# ESC.net
KiCad netlist of a schematic drawn in EAGLE
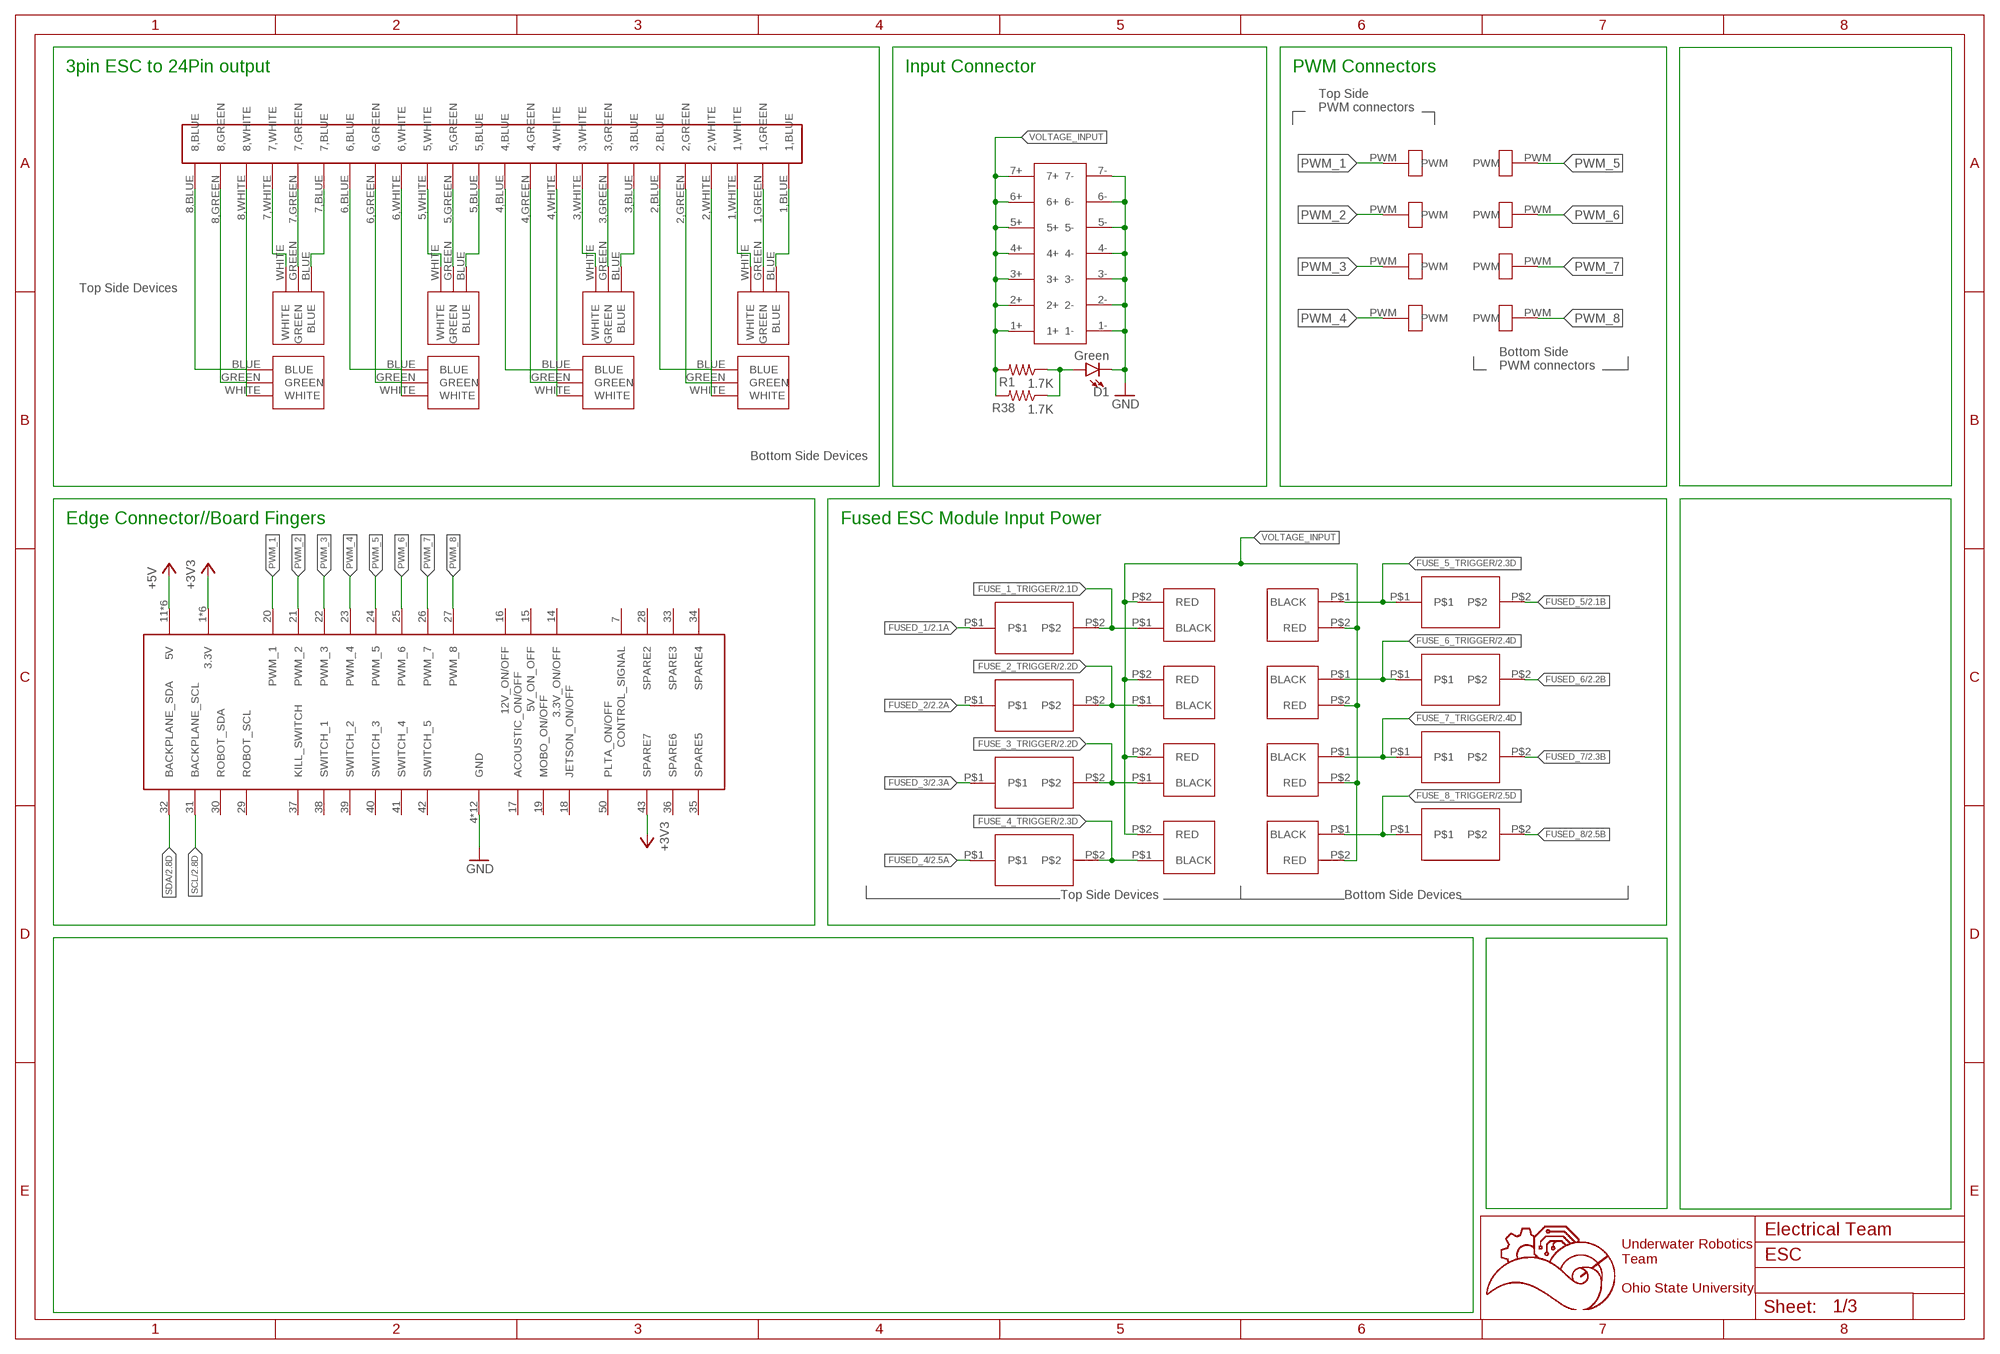
[diagram p0: schematic, sheet 1]
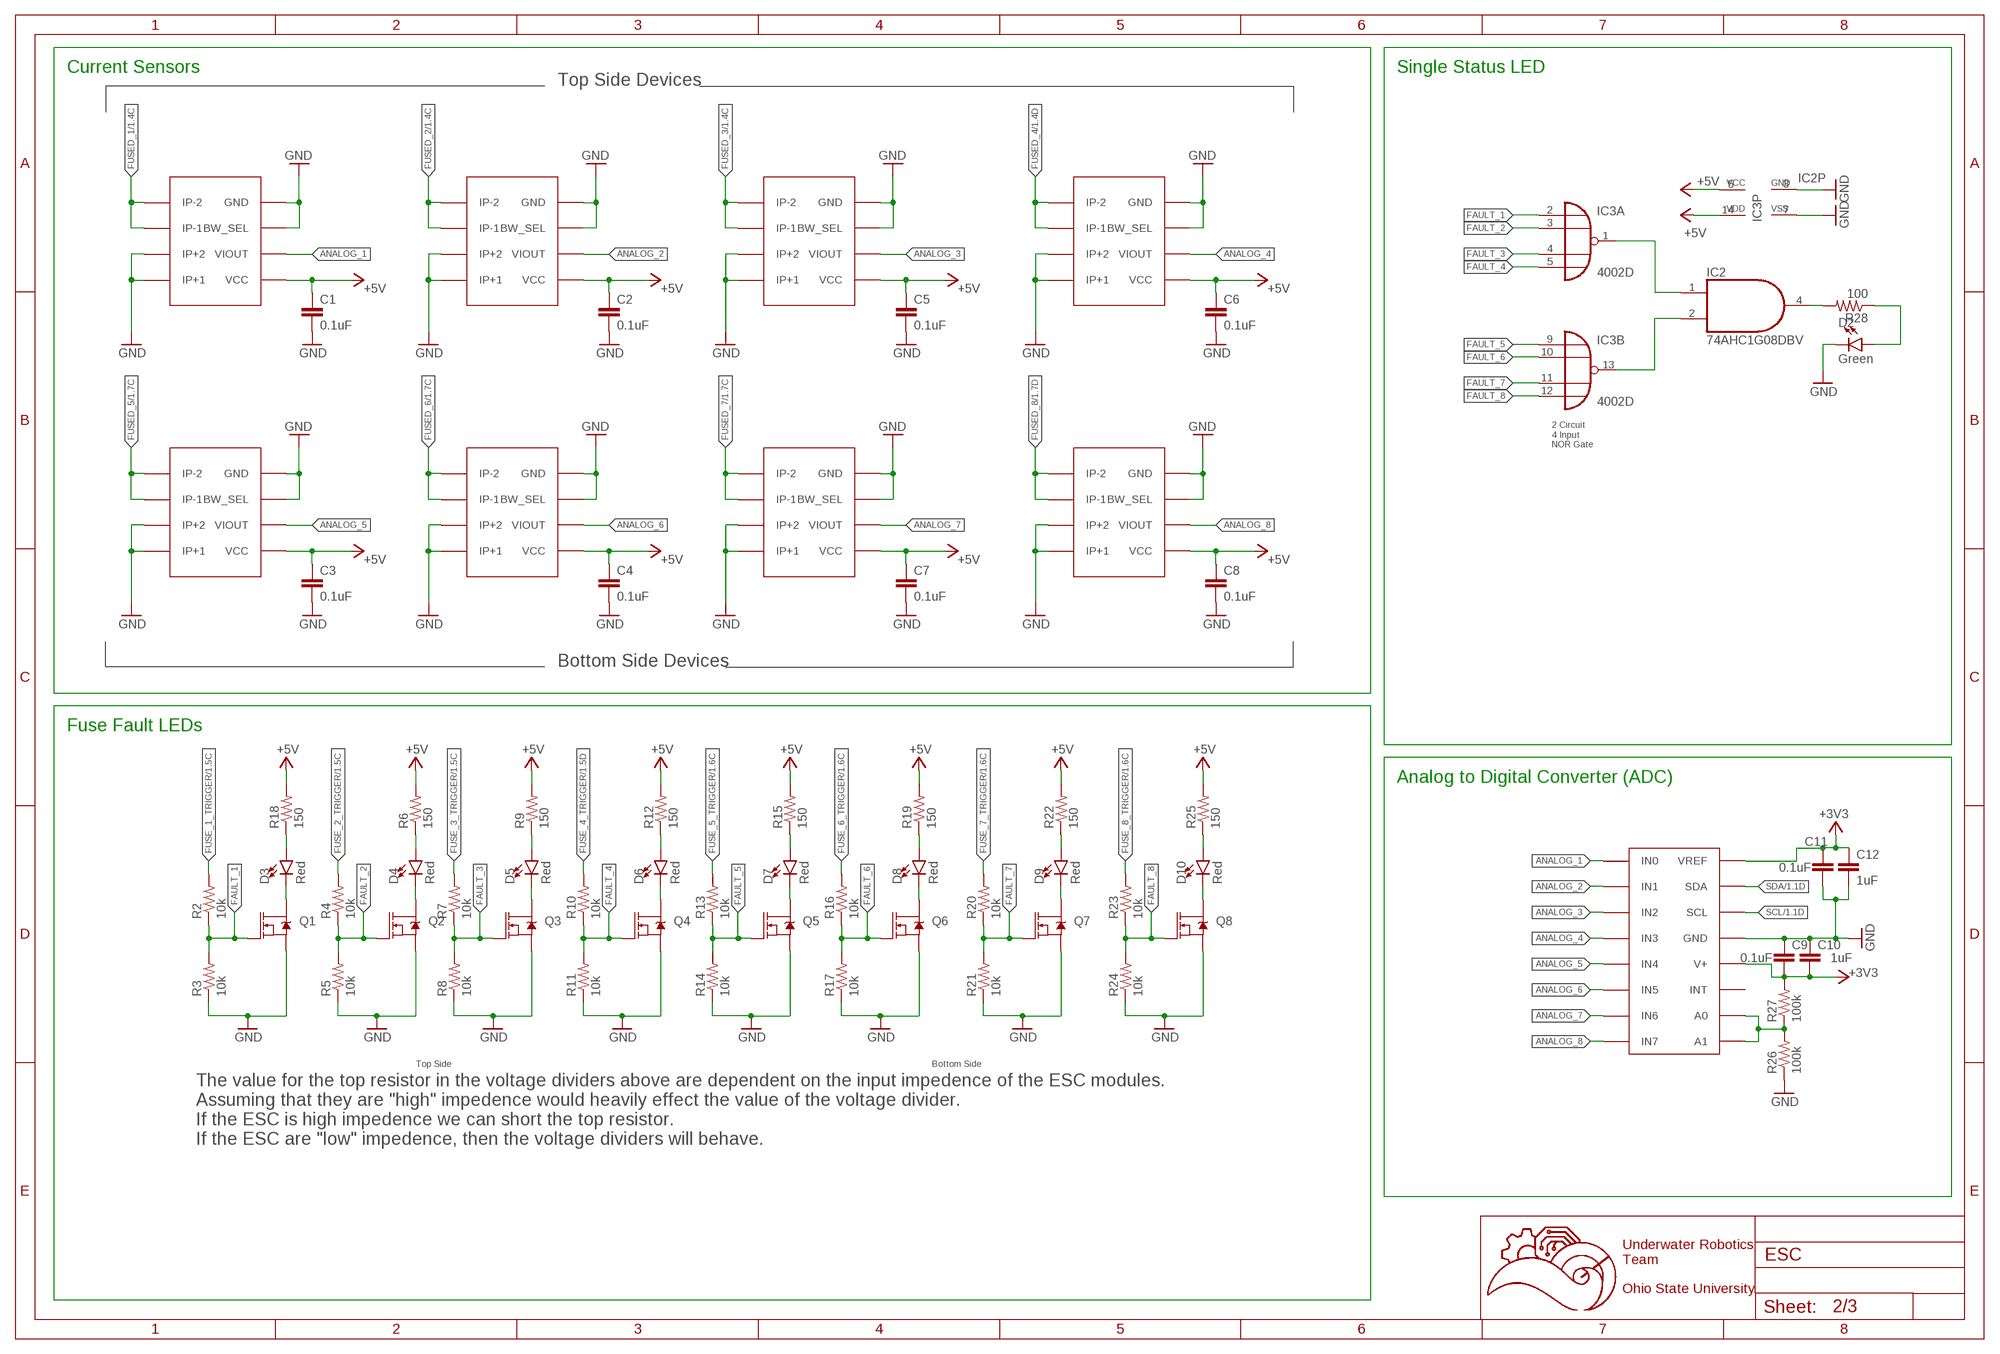
[diagram p1: schematic, sheet 2]
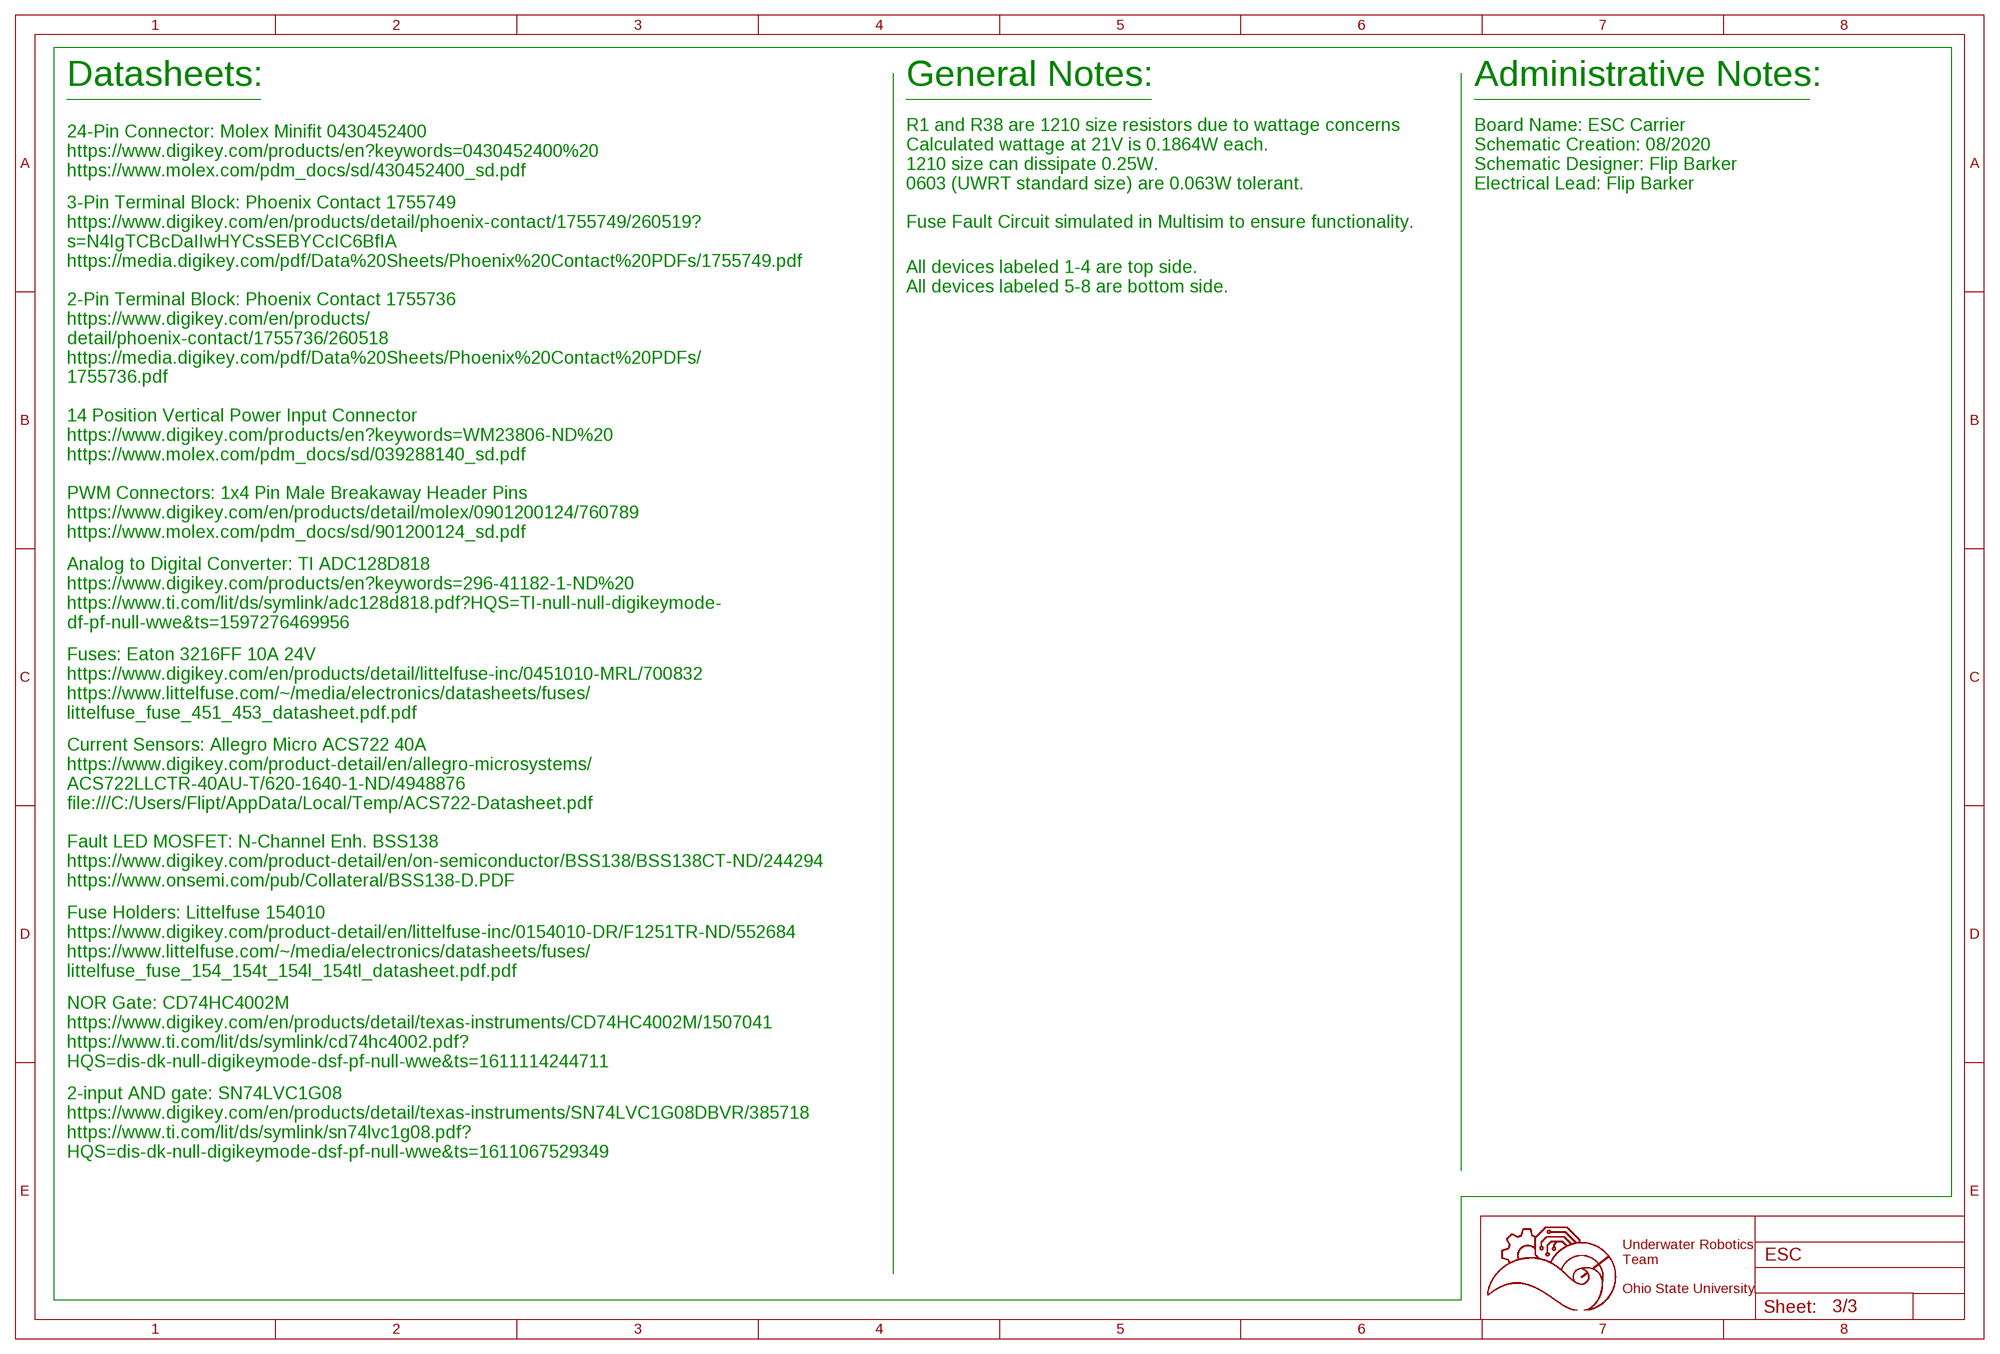
[diagram p2: schematic, sheet 3]

(export (version "E")
  (design (tool "Eeschema 10.0.6"))
  (components
    (comp (ref "C1")
      (value "0.1uF")
      (footprint "eagle-import:C0603")
      (libsource (lib "eagle-import") (part "C-EUC0603"))
    )
    (comp (ref "C2")
      (value "0.1uF")
      (footprint "eagle-import:C0603")
      (libsource (lib "eagle-import") (part "C-EUC0603"))
    )
    (comp (ref "C3")
      (value "0.1uF")
      (footprint "eagle-import:C0603")
      (libsource (lib "eagle-import") (part "C-EUC0603"))
    )
    (comp (ref "C4")
      (value "0.1uF")
      (footprint "eagle-import:C0603")
      (libsource (lib "eagle-import") (part "C-EUC0603"))
    )
    (comp (ref "C5")
      (value "0.1uF")
      (footprint "eagle-import:C0603")
      (libsource (lib "eagle-import") (part "C-EUC0603"))
    )
    (comp (ref "C6")
      (value "0.1uF")
      (footprint "eagle-import:C0603")
      (libsource (lib "eagle-import") (part "C-EUC0603"))
    )
    (comp (ref "C7")
      (value "0.1uF")
      (footprint "eagle-import:C0603")
      (libsource (lib "eagle-import") (part "C-EUC0603"))
    )
    (comp (ref "C8")
      (value "0.1uF")
      (footprint "eagle-import:C0603")
      (libsource (lib "eagle-import") (part "C-EUC0603"))
    )
    (comp (ref "C9")
      (value "0.1uF")
      (footprint "eagle-import:C0603")
      (libsource (lib "eagle-import") (part "C-EUC0603"))
    )
    (comp (ref "C10")
      (value "1uF")
      (footprint "eagle-import:C0603")
      (libsource (lib "eagle-import") (part "C-EUC0603"))
    )
    (comp (ref "C11")
      (value "0.1uF")
      (footprint "eagle-import:C0603")
      (libsource (lib "eagle-import") (part "C-EUC0603"))
    )
    (comp (ref "C12")
      (value "1uF")
      (footprint "eagle-import:C0603")
      (libsource (lib "eagle-import") (part "C-EUC0603"))
    )
    (comp (ref "CS_1")
      (value "ACS722")
      (footprint "eagle-import:SOIC-8")
      (libsource (lib "eagle-import") (part "ACS722"))
    )
    (comp (ref "CS_2")
      (value "ACS722")
      (footprint "eagle-import:SOIC-8")
      (libsource (lib "eagle-import") (part "ACS722"))
    )
    (comp (ref "CS_3")
      (value "ACS722")
      (footprint "eagle-import:SOIC-8")
      (libsource (lib "eagle-import") (part "ACS722"))
    )
    (comp (ref "CS_4")
      (value "ACS722")
      (footprint "eagle-import:SOIC-8")
      (libsource (lib "eagle-import") (part "ACS722"))
    )
    (comp (ref "CS_5")
      (value "ACS722")
      (footprint "eagle-import:SOIC-8")
      (libsource (lib "eagle-import") (part "ACS722"))
    )
    (comp (ref "CS_6")
      (value "ACS722")
      (footprint "eagle-import:SOIC-8")
      (libsource (lib "eagle-import") (part "ACS722"))
    )
    (comp (ref "CS_7")
      (value "ACS722")
      (footprint "eagle-import:SOIC-8")
      (libsource (lib "eagle-import") (part "ACS722"))
    )
    (comp (ref "CS_8")
      (value "ACS722")
      (footprint "eagle-import:SOIC-8")
      (libsource (lib "eagle-import") (part "ACS722"))
    )
    (comp (ref "D2")
      (value "Green")
      (footprint "eagle-import:LED-0603")
      (libsource (lib "eagle-import") (part "LED0603"))
    )
    (comp (ref "D3")
      (value "Red")
      (footprint "eagle-import:LED-0603")
      (libsource (lib "eagle-import") (part "LED0603"))
    )
    (comp (ref "D4")
      (value "Red")
      (footprint "eagle-import:LED-0603")
      (libsource (lib "eagle-import") (part "LED0603"))
    )
    (comp (ref "D5")
      (value "Red")
      (footprint "eagle-import:LED-0603")
      (libsource (lib "eagle-import") (part "LED0603"))
    )
    (comp (ref "D6")
      (value "Red")
      (footprint "eagle-import:LED-0603")
      (libsource (lib "eagle-import") (part "LED0603"))
    )
    (comp (ref "D7")
      (value "Red")
      (footprint "eagle-import:LED-0603")
      (libsource (lib "eagle-import") (part "LED0603"))
    )
    (comp (ref "D8")
      (value "Red")
      (footprint "eagle-import:LED-0603")
      (libsource (lib "eagle-import") (part "LED0603"))
    )
    (comp (ref "D9")
      (value "Red")
      (footprint "eagle-import:LED-0603")
      (libsource (lib "eagle-import") (part "LED0603"))
    )
    (comp (ref "D10")
      (value "Red")
      (footprint "eagle-import:LED-0603")
      (libsource (lib "eagle-import") (part "LED0603"))
    )
    (comp (ref "IC2")
      (value "74AHC1G08DBV")
      (footprint "eagle-import:SOT23-5")
      (libsource (lib "eagle-import") (part "741G08DBVAHC"))
    )
    (comp (ref "IC3")
      (value "4002D")
      (footprint "eagle-import:SO14")
      (libsource (lib "eagle-import") (part "4002D"))
    )
    (comp (ref "Q1")
      (value "5.8A/30V/35mΩ")
      (footprint "eagle-import:SOT23-3")
      (libsource (lib "eagle-import") (part "MOSFET-NCH-AO3404A"))
    )
    (comp (ref "Q2")
      (value "5.8A/30V/35mΩ")
      (footprint "eagle-import:SOT23-3")
      (libsource (lib "eagle-import") (part "MOSFET-NCH-AO3404A"))
    )
    (comp (ref "Q3")
      (value "5.8A/30V/35mΩ")
      (footprint "eagle-import:SOT23-3")
      (libsource (lib "eagle-import") (part "MOSFET-NCH-AO3404A"))
    )
    (comp (ref "Q4")
      (value "5.8A/30V/35mΩ")
      (footprint "eagle-import:SOT23-3")
      (libsource (lib "eagle-import") (part "MOSFET-NCH-AO3404A"))
    )
    (comp (ref "Q5")
      (value "5.8A/30V/35mΩ")
      (footprint "eagle-import:SOT23-3")
      (libsource (lib "eagle-import") (part "MOSFET-NCH-AO3404A"))
    )
    (comp (ref "Q6")
      (value "5.8A/30V/35mΩ")
      (footprint "eagle-import:SOT23-3")
      (libsource (lib "eagle-import") (part "MOSFET-NCH-AO3404A"))
    )
    (comp (ref "Q7")
      (value "5.8A/30V/35mΩ")
      (footprint "eagle-import:SOT23-3")
      (libsource (lib "eagle-import") (part "MOSFET-NCH-AO3404A"))
    )
    (comp (ref "Q8")
      (value "5.8A/30V/35mΩ")
      (footprint "eagle-import:SOT23-3")
      (libsource (lib "eagle-import") (part "MOSFET-NCH-AO3404A"))
    )
    (comp (ref "R2")
      (value "10k")
      (footprint "eagle-import:R0603")
      (libsource (lib "eagle-import") (part "R-US_R0603"))
    )
    (comp (ref "R3")
      (value "10k")
      (footprint "eagle-import:R0603")
      (libsource (lib "eagle-import") (part "R-US_R0603"))
    )
    (comp (ref "R4")
      (value "10k")
      (footprint "eagle-import:R0603")
      (libsource (lib "eagle-import") (part "R-US_R0603"))
    )
    (comp (ref "R5")
      (value "10k")
      (footprint "eagle-import:R0603")
      (libsource (lib "eagle-import") (part "R-US_R0603"))
    )
    (comp (ref "R6")
      (value "150")
      (footprint "eagle-import:R0603")
      (libsource (lib "eagle-import") (part "R-US_R0603"))
    )
    (comp (ref "R7")
      (value "10k")
      (footprint "eagle-import:R0603")
      (libsource (lib "eagle-import") (part "R-US_R0603"))
    )
    (comp (ref "R8")
      (value "10k")
      (footprint "eagle-import:R0603")
      (libsource (lib "eagle-import") (part "R-US_R0603"))
    )
    (comp (ref "R9")
      (value "150")
      (footprint "eagle-import:R0603")
      (libsource (lib "eagle-import") (part "R-US_R0603"))
    )
    (comp (ref "R10")
      (value "10k")
      (footprint "eagle-import:R0603")
      (libsource (lib "eagle-import") (part "R-US_R0603"))
    )
    (comp (ref "R11")
      (value "10k")
      (footprint "eagle-import:R0603")
      (libsource (lib "eagle-import") (part "R-US_R0603"))
    )
    (comp (ref "R12")
      (value "150")
      (footprint "eagle-import:R0603")
      (libsource (lib "eagle-import") (part "R-US_R0603"))
    )
    (comp (ref "R13")
      (value "10k")
      (footprint "eagle-import:R0603")
      (libsource (lib "eagle-import") (part "R-US_R0603"))
    )
    (comp (ref "R14")
      (value "10k")
      (footprint "eagle-import:R0603")
      (libsource (lib "eagle-import") (part "R-US_R0603"))
    )
    (comp (ref "R15")
      (value "150")
      (footprint "eagle-import:R0603")
      (libsource (lib "eagle-import") (part "R-US_R0603"))
    )
    (comp (ref "R16")
      (value "10k")
      (footprint "eagle-import:R0603")
      (libsource (lib "eagle-import") (part "R-US_R0603"))
    )
    (comp (ref "R17")
      (value "10k")
      (footprint "eagle-import:R0603")
      (libsource (lib "eagle-import") (part "R-US_R0603"))
    )
    (comp (ref "R18")
      (value "150")
      (footprint "eagle-import:R0603")
      (libsource (lib "eagle-import") (part "R-US_R0603"))
    )
    (comp (ref "R19")
      (value "150")
      (footprint "eagle-import:R0603")
      (libsource (lib "eagle-import") (part "R-US_R0603"))
    )
    (comp (ref "R20")
      (value "10k")
      (footprint "eagle-import:R0603")
      (libsource (lib "eagle-import") (part "R-US_R0603"))
    )
    (comp (ref "R21")
      (value "10k")
      (footprint "eagle-import:R0603")
      (libsource (lib "eagle-import") (part "R-US_R0603"))
    )
    (comp (ref "R22")
      (value "150")
      (footprint "eagle-import:R0603")
      (libsource (lib "eagle-import") (part "R-US_R0603"))
    )
    (comp (ref "R23")
      (value "10k")
      (footprint "eagle-import:R0603")
      (libsource (lib "eagle-import") (part "R-US_R0603"))
    )
    (comp (ref "R24")
      (value "10k")
      (footprint "eagle-import:R0603")
      (libsource (lib "eagle-import") (part "R-US_R0603"))
    )
    (comp (ref "R25")
      (value "150")
      (footprint "eagle-import:R0603")
      (libsource (lib "eagle-import") (part "R-US_R0603"))
    )
    (comp (ref "R26")
      (value "100k")
      (footprint "eagle-import:R0603")
      (libsource (lib "eagle-import") (part "R-US_R0603"))
    )
    (comp (ref "R27")
      (value "100k")
      (footprint "eagle-import:R0603")
      (libsource (lib "eagle-import") (part "R-US_R0603"))
    )
    (comp (ref "R28")
      (value "100")
      (footprint "eagle-import:R0603")
      (libsource (lib "eagle-import") (part "R-US_R0603"))
    )
    (comp (ref "U$11")
      (value "ADC128D818")
      (footprint "eagle-import:TSSOP-16")
      (libsource (lib "eagle-import") (part "ADC128D818"))
    )
    (comp (ref "2-PIN_1")
      (value "1755736")
      (footprint "eagle-import:1755736")
      (libsource (lib "eagle-import") (part "1755736"))
    )
    (comp (ref "2-PIN_2")
      (value "1755736")
      (footprint "eagle-import:1755736")
      (libsource (lib "eagle-import") (part "1755736"))
    )
    (comp (ref "2-PIN_3")
      (value "1755736")
      (footprint "eagle-import:1755736")
      (libsource (lib "eagle-import") (part "1755736"))
    )
    (comp (ref "2-PIN_4")
      (value "1755736")
      (footprint "eagle-import:1755736")
      (libsource (lib "eagle-import") (part "1755736"))
    )
    (comp (ref "2-PIN_5")
      (value "1755736")
      (footprint "eagle-import:1755736")
      (libsource (lib "eagle-import") (part "1755736"))
    )
    (comp (ref "2-PIN_6")
      (value "1755736")
      (footprint "eagle-import:1755736")
      (libsource (lib "eagle-import") (part "1755736"))
    )
    (comp (ref "2-PIN_7")
      (value "1755736")
      (footprint "eagle-import:1755736")
      (libsource (lib "eagle-import") (part "1755736"))
    )
    (comp (ref "2-PIN_8")
      (value "1755736")
      (footprint "eagle-import:1755736")
      (libsource (lib "eagle-import") (part "1755736"))
    )
    (comp (ref "3-PIN_1")
      (value "1755749")
      (footprint "eagle-import:1755749")
      (libsource (lib "eagle-import") (part "1755749"))
    )
    (comp (ref "3-PIN_2")
      (value "1755749")
      (footprint "eagle-import:1755749")
      (libsource (lib "eagle-import") (part "1755749"))
    )
    (comp (ref "3-PIN_3")
      (value "1755749")
      (footprint "eagle-import:1755749")
      (libsource (lib "eagle-import") (part "1755749"))
    )
    (comp (ref "3-PIN_4")
      (value "1755749")
      (footprint "eagle-import:1755749")
      (libsource (lib "eagle-import") (part "1755749"))
    )
    (comp (ref "3-PIN_5")
      (value "1755749")
      (footprint "eagle-import:1755749")
      (libsource (lib "eagle-import") (part "1755749"))
    )
    (comp (ref "3-PIN_6")
      (value "1755749")
      (footprint "eagle-import:1755749")
      (libsource (lib "eagle-import") (part "1755749"))
    )
    (comp (ref "3-PIN_7")
      (value "1755749")
      (footprint "eagle-import:1755749")
      (libsource (lib "eagle-import") (part "1755749"))
    )
    (comp (ref "3-PIN_8")
      (value "1755749")
      (footprint "eagle-import:1755749")
      (libsource (lib "eagle-import") (part "1755749"))
    )
    (comp (ref "24-PIN_CONNECTOR")
      (value "24PINCONVERTER")
      (footprint "eagle-import:24PINCONVERTER")
      (libsource (lib "eagle-import") (part "24PINCONVERTER"))
    )
    (comp (ref "D1")
      (value "Green")
      (footprint "eagle-import:LED-0603")
      (libsource (lib "eagle-import") (part "LED0603"))
    )
    (comp (ref "EDGE_CONNECTOR")
      (value "5530843-EDGE")
      (footprint "eagle-import:5530843-6-BOARDFINGERS")
      (libsource (lib "eagle-import") (part "5530843-EDGE"))
    )
    (comp (ref "F1")
      (value "1206FUSEHOLDER")
      (footprint "eagle-import:1206FUSEHOLDER")
      (libsource (lib "eagle-import") (part "1206FUSEHOLDER"))
    )
    (comp (ref "F2")
      (value "1206FUSEHOLDER")
      (footprint "eagle-import:1206FUSEHOLDER")
      (libsource (lib "eagle-import") (part "1206FUSEHOLDER"))
    )
    (comp (ref "F3")
      (value "1206FUSEHOLDER")
      (footprint "eagle-import:1206FUSEHOLDER")
      (libsource (lib "eagle-import") (part "1206FUSEHOLDER"))
    )
    (comp (ref "F4")
      (value "1206FUSEHOLDER")
      (footprint "eagle-import:1206FUSEHOLDER")
      (libsource (lib "eagle-import") (part "1206FUSEHOLDER"))
    )
    (comp (ref "F5")
      (value "1206FUSEHOLDER")
      (footprint "eagle-import:1206FUSEHOLDER")
      (libsource (lib "eagle-import") (part "1206FUSEHOLDER"))
    )
    (comp (ref "F6")
      (value "1206FUSEHOLDER")
      (footprint "eagle-import:1206FUSEHOLDER")
      (libsource (lib "eagle-import") (part "1206FUSEHOLDER"))
    )
    (comp (ref "F7")
      (value "1206FUSEHOLDER")
      (footprint "eagle-import:1206FUSEHOLDER")
      (libsource (lib "eagle-import") (part "1206FUSEHOLDER"))
    )
    (comp (ref "F8")
      (value "1206FUSEHOLDER")
      (footprint "eagle-import:1206FUSEHOLDER")
      (libsource (lib "eagle-import") (part "1206FUSEHOLDER"))
    )
    (comp (ref "POWER_INPUT")
      (value "14PIN_VERT")
      (footprint "eagle-import:14PIN_VERT")
      (libsource (lib "eagle-import") (part "14PIN_VERT"))
    )
    (comp (ref "R1")
      (value "1.7K")
      (footprint "eagle-import:R1210")
      (libsource (lib "eagle-import") (part "R-US_R1210"))
    )
    (comp (ref "R38")
      (value "1.7K")
      (footprint "eagle-import:R1210")
      (libsource (lib "eagle-import") (part "R-US_R1210"))
    )
    (comp (ref "U$1")
      (value "MALE1PINHEADER")
      (footprint "eagle-import:MALE1PINHEADER")
      (libsource (lib "eagle-import") (part "MALE1PINHEADER"))
    )
    (comp (ref "U$2")
      (value "MALE1PINHEADER")
      (footprint "eagle-import:MALE1PINHEADER")
      (libsource (lib "eagle-import") (part "MALE1PINHEADER"))
    )
    (comp (ref "U$3")
      (value "MALE1PINHEADER")
      (footprint "eagle-import:MALE1PINHEADER")
      (libsource (lib "eagle-import") (part "MALE1PINHEADER"))
    )
    (comp (ref "U$4")
      (value "MALE1PINHEADER")
      (footprint "eagle-import:MALE1PINHEADER")
      (libsource (lib "eagle-import") (part "MALE1PINHEADER"))
    )
    (comp (ref "U$5")
      (value "MALE1PINHEADER")
      (footprint "eagle-import:MALE1PINHEADER")
      (libsource (lib "eagle-import") (part "MALE1PINHEADER"))
    )
    (comp (ref "U$6")
      (value "MALE1PINHEADER")
      (footprint "eagle-import:MALE1PINHEADER")
      (libsource (lib "eagle-import") (part "MALE1PINHEADER"))
    )
    (comp (ref "U$7")
      (value "MALE1PINHEADER")
      (footprint "eagle-import:MALE1PINHEADER")
      (libsource (lib "eagle-import") (part "MALE1PINHEADER"))
    )
    (comp (ref "U$8")
      (value "MALE1PINHEADER")
      (footprint "eagle-import:MALE1PINHEADER")
      (libsource (lib "eagle-import") (part "MALE1PINHEADER"))
    )
  )
  (nets
    (net (code "1") (name "+3V3") (class "Default")
      (node (ref "C10") (pin "2") (pinfunction "2_2") (pintype "passive"))
      (node (ref "C11") (pin "1") (pinfunction "1_1") (pintype "passive"))
      (node (ref "C12") (pin "1") (pinfunction "1_1") (pintype "passive"))
      (node (ref "C9") (pin "2") (pinfunction "2_2") (pintype "passive"))
      (node (ref "EDGE_CONNECTOR") (pin "1") (pinfunction "3.3V_1") (pintype "bidirectional"))
      (node (ref "EDGE_CONNECTOR") (pin "2") (pinfunction "3.3V_2") (pintype "bidirectional"))
      (node (ref "EDGE_CONNECTOR") (pin "3") (pinfunction "3.3V_3") (pintype "bidirectional"))
      (node (ref "EDGE_CONNECTOR") (pin "43") (pinfunction "SPARE7_43") (pintype "bidirectional"))
      (node (ref "EDGE_CONNECTOR") (pin "54") (pinfunction "3.3V_54") (pintype "bidirectional"))
      (node (ref "EDGE_CONNECTOR") (pin "55") (pinfunction "3.3V_55") (pintype "bidirectional"))
      (node (ref "EDGE_CONNECTOR") (pin "56") (pinfunction "3.3V_56") (pintype "bidirectional"))
      (node (ref "R27") (pin "2") (pinfunction "2_2") (pintype "passive"))
      (node (ref "U$11") (pin "V+") (pinfunction "V+_V+") (pintype "bidirectional"))
      (node (ref "U$11") (pin "VREF") (pinfunction "VREF_VREF") (pintype "bidirectional"))
    )
    (net (code "2") (name "+5V") (class "Default")
      (node (ref "C1") (pin "1") (pinfunction "1_1") (pintype "passive"))
      (node (ref "C2") (pin "1") (pinfunction "1_1") (pintype "passive"))
      (node (ref "C3") (pin "1") (pinfunction "1_1") (pintype "passive"))
      (node (ref "C4") (pin "1") (pinfunction "1_1") (pintype "passive"))
      (node (ref "C5") (pin "1") (pinfunction "1_1") (pintype "passive"))
      (node (ref "C6") (pin "1") (pinfunction "1_1") (pintype "passive"))
      (node (ref "C7") (pin "1") (pinfunction "1_1") (pintype "passive"))
      (node (ref "C8") (pin "1") (pinfunction "1_1") (pintype "passive"))
      (node (ref "CS_1") (pin "VCC") (pinfunction "VCC_VCC") (pintype "bidirectional"))
      (node (ref "CS_2") (pin "VCC") (pinfunction "VCC_VCC") (pintype "bidirectional"))
      (node (ref "CS_3") (pin "VCC") (pinfunction "VCC_VCC") (pintype "bidirectional"))
      (node (ref "CS_4") (pin "VCC") (pinfunction "VCC_VCC") (pintype "bidirectional"))
      (node (ref "CS_5") (pin "VCC") (pinfunction "VCC_VCC") (pintype "bidirectional"))
      (node (ref "CS_6") (pin "VCC") (pinfunction "VCC_VCC") (pintype "bidirectional"))
      (node (ref "CS_7") (pin "VCC") (pinfunction "VCC_VCC") (pintype "bidirectional"))
      (node (ref "CS_8") (pin "VCC") (pinfunction "VCC_VCC") (pintype "bidirectional"))
      (node (ref "EDGE_CONNECTOR") (pin "11") (pinfunction "5V_11") (pintype "bidirectional"))
      (node (ref "EDGE_CONNECTOR") (pin "12") (pinfunction "5V_12") (pintype "bidirectional"))
      (node (ref "EDGE_CONNECTOR") (pin "13") (pinfunction "5V_13") (pintype "bidirectional"))
      (node (ref "EDGE_CONNECTOR") (pin "44") (pinfunction "5V_44") (pintype "bidirectional"))
      (node (ref "EDGE_CONNECTOR") (pin "45") (pinfunction "5V_45") (pintype "bidirectional"))
      (node (ref "EDGE_CONNECTOR") (pin "46") (pinfunction "5V_46") (pintype "bidirectional"))
      (node (ref "IC2") (pin "5") (pinfunction "VCC_5") (pintype "power_in"))
      (node (ref "IC3") (pin "14") (pinfunction "VDD_14") (pintype "power_in"))
      (node (ref "R12") (pin "2") (pinfunction "2_2") (pintype "passive"))
      (node (ref "R15") (pin "2") (pinfunction "2_2") (pintype "passive"))
      (node (ref "R18") (pin "2") (pinfunction "2_2") (pintype "passive"))
      (node (ref "R19") (pin "2") (pinfunction "2_2") (pintype "passive"))
      (node (ref "R22") (pin "2") (pinfunction "2_2") (pintype "passive"))
      (node (ref "R25") (pin "2") (pinfunction "2_2") (pintype "passive"))
      (node (ref "R6") (pin "2") (pinfunction "2_2") (pintype "passive"))
      (node (ref "R9") (pin "2") (pinfunction "2_2") (pintype "passive"))
    )
    (net (code "3") (name "ANALOG_1") (class "Default")
      (node (ref "CS_1") (pin "VIOUT") (pinfunction "VIOUT_VIOUT") (pintype "bidirectional"))
      (node (ref "U$11") (pin "IN0") (pinfunction "IN0_IN0") (pintype "bidirectional"))
    )
    (net (code "4") (name "ANALOG_2") (class "Default")
      (node (ref "CS_2") (pin "VIOUT") (pinfunction "VIOUT_VIOUT") (pintype "bidirectional"))
      (node (ref "U$11") (pin "IN1") (pinfunction "IN1_IN1") (pintype "bidirectional"))
    )
    (net (code "5") (name "ANALOG_3") (class "Default")
      (node (ref "CS_3") (pin "VIOUT") (pinfunction "VIOUT_VIOUT") (pintype "bidirectional"))
      (node (ref "U$11") (pin "IN2") (pinfunction "IN2_IN2") (pintype "bidirectional"))
    )
    (net (code "6") (name "ANALOG_4") (class "Default")
      (node (ref "CS_4") (pin "VIOUT") (pinfunction "VIOUT_VIOUT") (pintype "bidirectional"))
      (node (ref "U$11") (pin "IN3") (pinfunction "IN3_IN3") (pintype "bidirectional"))
    )
    (net (code "7") (name "ANALOG_5") (class "Default")
      (node (ref "CS_5") (pin "VIOUT") (pinfunction "VIOUT_VIOUT") (pintype "bidirectional"))
      (node (ref "U$11") (pin "IN4") (pinfunction "IN4_IN4") (pintype "bidirectional"))
    )
    (net (code "8") (name "ANALOG_6") (class "Default")
      (node (ref "CS_6") (pin "VIOUT") (pinfunction "VIOUT_VIOUT") (pintype "bidirectional"))
      (node (ref "U$11") (pin "IN5") (pinfunction "IN5_IN5") (pintype "bidirectional"))
    )
    (net (code "9") (name "ANALOG_7") (class "Default")
      (node (ref "CS_7") (pin "VIOUT") (pinfunction "VIOUT_VIOUT") (pintype "bidirectional"))
      (node (ref "U$11") (pin "IN6") (pinfunction "IN6_IN6") (pintype "bidirectional"))
    )
    (net (code "10") (name "ANALOG_8") (class "Default")
      (node (ref "CS_8") (pin "VIOUT") (pinfunction "VIOUT_VIOUT") (pintype "bidirectional"))
      (node (ref "U$11") (pin "IN7") (pinfunction "IN7_IN7") (pintype "bidirectional"))
    )
    (net (code "11") (name "FAULT_1") (class "Default")
      (node (ref "IC3") (pin "2") (pinfunction "I0_2") (pintype "input"))
      (node (ref "Q1") (pin "1") (pinfunction "G_1") (pintype "bidirectional"))
      (node (ref "R2") (pin "1") (pinfunction "1_1") (pintype "passive"))
      (node (ref "R3") (pin "2") (pinfunction "2_2") (pintype "passive"))
    )
    (net (code "12") (name "FAULT_2") (class "Default")
      (node (ref "IC3") (pin "3") (pinfunction "I1_3") (pintype "input"))
      (node (ref "Q2") (pin "1") (pinfunction "G_1") (pintype "bidirectional"))
      (node (ref "R4") (pin "1") (pinfunction "1_1") (pintype "passive"))
      (node (ref "R5") (pin "2") (pinfunction "2_2") (pintype "passive"))
    )
    (net (code "13") (name "FAULT_3") (class "Default")
      (node (ref "IC3") (pin "4") (pinfunction "I2_4") (pintype "input"))
      (node (ref "Q3") (pin "1") (pinfunction "G_1") (pintype "bidirectional"))
      (node (ref "R7") (pin "1") (pinfunction "1_1") (pintype "passive"))
      (node (ref "R8") (pin "2") (pinfunction "2_2") (pintype "passive"))
    )
    (net (code "14") (name "FAULT_4") (class "Default")
      (node (ref "IC3") (pin "5") (pinfunction "I3_5") (pintype "input"))
      (node (ref "Q4") (pin "1") (pinfunction "G_1") (pintype "bidirectional"))
      (node (ref "R10") (pin "1") (pinfunction "1_1") (pintype "passive"))
      (node (ref "R11") (pin "2") (pinfunction "2_2") (pintype "passive"))
    )
    (net (code "15") (name "FAULT_5") (class "Default")
      (node (ref "IC3") (pin "9") (pinfunction "I0_9") (pintype "input"))
      (node (ref "Q5") (pin "1") (pinfunction "G_1") (pintype "bidirectional"))
      (node (ref "R13") (pin "1") (pinfunction "1_1") (pintype "passive"))
      (node (ref "R14") (pin "2") (pinfunction "2_2") (pintype "passive"))
    )
    (net (code "16") (name "FAULT_6") (class "Default")
      (node (ref "IC3") (pin "10") (pinfunction "I1_10") (pintype "input"))
      (node (ref "Q6") (pin "1") (pinfunction "G_1") (pintype "bidirectional"))
      (node (ref "R16") (pin "1") (pinfunction "1_1") (pintype "passive"))
      (node (ref "R17") (pin "2") (pinfunction "2_2") (pintype "passive"))
    )
    (net (code "17") (name "FAULT_7") (class "Default")
      (node (ref "IC3") (pin "11") (pinfunction "I2_11") (pintype "input"))
      (node (ref "Q7") (pin "1") (pinfunction "G_1") (pintype "bidirectional"))
      (node (ref "R20") (pin "1") (pinfunction "1_1") (pintype "passive"))
      (node (ref "R21") (pin "2") (pinfunction "2_2") (pintype "passive"))
    )
    (net (code "18") (name "FAULT_8") (class "Default")
      (node (ref "IC3") (pin "12") (pinfunction "I3_12") (pintype "input"))
      (node (ref "Q8") (pin "1") (pinfunction "G_1") (pintype "bidirectional"))
      (node (ref "R23") (pin "1") (pinfunction "1_1") (pintype "passive"))
      (node (ref "R24") (pin "2") (pinfunction "2_2") (pintype "passive"))
    )
    (net (code "19") (name "FUSED_1") (class "Default")
      (node (ref "CS_1") (pin "IP-1") (pinfunction "IP-1_IP-1") (pintype "bidirectional"))
      (node (ref "CS_1") (pin "IP-2") (pinfunction "IP-2_IP-2") (pintype "bidirectional"))
      (node (ref "F1") (pin "P$1") (pinfunction "P$1_P$1") (pintype "bidirectional"))
    )
    (net (code "20") (name "FUSED_2") (class "Default")
      (node (ref "CS_2") (pin "IP-1") (pinfunction "IP-1_IP-1") (pintype "bidirectional"))
      (node (ref "CS_2") (pin "IP-2") (pinfunction "IP-2_IP-2") (pintype "bidirectional"))
      (node (ref "F2") (pin "P$1") (pinfunction "P$1_P$1") (pintype "bidirectional"))
    )
    (net (code "21") (name "FUSED_3") (class "Default")
      (node (ref "CS_3") (pin "IP-1") (pinfunction "IP-1_IP-1") (pintype "bidirectional"))
      (node (ref "CS_3") (pin "IP-2") (pinfunction "IP-2_IP-2") (pintype "bidirectional"))
      (node (ref "F3") (pin "P$1") (pinfunction "P$1_P$1") (pintype "bidirectional"))
    )
    (net (code "22") (name "FUSED_4") (class "Default")
      (node (ref "CS_4") (pin "IP-1") (pinfunction "IP-1_IP-1") (pintype "bidirectional"))
      (node (ref "CS_4") (pin "IP-2") (pinfunction "IP-2_IP-2") (pintype "bidirectional"))
      (node (ref "F4") (pin "P$1") (pinfunction "P$1_P$1") (pintype "bidirectional"))
    )
    (net (code "23") (name "FUSED_5") (class "Default")
      (node (ref "CS_5") (pin "IP-1") (pinfunction "IP-1_IP-1") (pintype "bidirectional"))
      (node (ref "CS_5") (pin "IP-2") (pinfunction "IP-2_IP-2") (pintype "bidirectional"))
      (node (ref "F5") (pin "P$2") (pinfunction "P$2_P$2") (pintype "bidirectional"))
    )
    (net (code "24") (name "FUSED_6") (class "Default")
      (node (ref "CS_6") (pin "IP-1") (pinfunction "IP-1_IP-1") (pintype "bidirectional"))
      (node (ref "CS_6") (pin "IP-2") (pinfunction "IP-2_IP-2") (pintype "bidirectional"))
      (node (ref "F6") (pin "P$2") (pinfunction "P$2_P$2") (pintype "bidirectional"))
    )
    (net (code "25") (name "FUSED_7") (class "Default")
      (node (ref "CS_7") (pin "IP-1") (pinfunction "IP-1_IP-1") (pintype "bidirectional"))
      (node (ref "CS_7") (pin "IP-2") (pinfunction "IP-2_IP-2") (pintype "bidirectional"))
      (node (ref "F7") (pin "P$2") (pinfunction "P$2_P$2") (pintype "bidirectional"))
    )
    (net (code "26") (name "FUSED_8") (class "Default")
      (node (ref "CS_8") (pin "IP-1") (pinfunction "IP-1_IP-1") (pintype "bidirectional"))
      (node (ref "CS_8") (pin "IP-2") (pinfunction "IP-2_IP-2") (pintype "bidirectional"))
      (node (ref "F8") (pin "P$2") (pinfunction "P$2_P$2") (pintype "bidirectional"))
    )
    (net (code "27") (name "FUSE_1_TRIGGER") (class "Default")
      (node (ref "2-PIN_1") (pin "P$1") (pinfunction "BLACK_P$1") (pintype "bidirectional"))
      (node (ref "F1") (pin "P$2") (pinfunction "P$2_P$2") (pintype "bidirectional"))
      (node (ref "R2") (pin "2") (pinfunction "2_2") (pintype "passive"))
    )
    (net (code "28") (name "FUSE_2_TRIGGER") (class "Default")
      (node (ref "2-PIN_2") (pin "P$1") (pinfunction "BLACK_P$1") (pintype "bidirectional"))
      (node (ref "F2") (pin "P$2") (pinfunction "P$2_P$2") (pintype "bidirectional"))
      (node (ref "R4") (pin "2") (pinfunction "2_2") (pintype "passive"))
    )
    (net (code "29") (name "FUSE_3_TRIGGER") (class "Default")
      (node (ref "2-PIN_3") (pin "P$1") (pinfunction "BLACK_P$1") (pintype "bidirectional"))
      (node (ref "F3") (pin "P$2") (pinfunction "P$2_P$2") (pintype "bidirectional"))
      (node (ref "R7") (pin "2") (pinfunction "2_2") (pintype "passive"))
    )
    (net (code "30") (name "FUSE_4_TRIGGER") (class "Default")
      (node (ref "2-PIN_4") (pin "P$1") (pinfunction "BLACK_P$1") (pintype "bidirectional"))
      (node (ref "F4") (pin "P$2") (pinfunction "P$2_P$2") (pintype "bidirectional"))
      (node (ref "R10") (pin "2") (pinfunction "2_2") (pintype "passive"))
    )
    (net (code "31") (name "FUSE_5_TRIGGER") (class "Default")
      (node (ref "2-PIN_5") (pin "P$1") (pinfunction "BLACK_P$1") (pintype "bidirectional"))
      (node (ref "F5") (pin "P$1") (pinfunction "P$1_P$1") (pintype "bidirectional"))
      (node (ref "R13") (pin "2") (pinfunction "2_2") (pintype "passive"))
    )
    (net (code "32") (name "FUSE_6_TRIGGER") (class "Default")
      (node (ref "2-PIN_6") (pin "P$1") (pinfunction "BLACK_P$1") (pintype "bidirectional"))
      (node (ref "F6") (pin "P$1") (pinfunction "P$1_P$1") (pintype "bidirectional"))
      (node (ref "R16") (pin "2") (pinfunction "2_2") (pintype "passive"))
    )
    (net (code "33") (name "FUSE_7_TRIGGER") (class "Default")
      (node (ref "2-PIN_7") (pin "P$1") (pinfunction "BLACK_P$1") (pintype "bidirectional"))
      (node (ref "F7") (pin "P$1") (pinfunction "P$1_P$1") (pintype "bidirectional"))
      (node (ref "R20") (pin "2") (pinfunction "2_2") (pintype "passive"))
    )
    (net (code "34") (name "FUSE_8_TRIGGER") (class "Default")
      (node (ref "2-PIN_8") (pin "P$1") (pinfunction "BLACK_P$1") (pintype "bidirectional"))
      (node (ref "F8") (pin "P$1") (pinfunction "P$1_P$1") (pintype "bidirectional"))
      (node (ref "R23") (pin "2") (pinfunction "2_2") (pintype "passive"))
    )
    (net (code "35") (name "GND") (class "Default")
      (node (ref "C1") (pin "2") (pinfunction "2_2") (pintype "passive"))
      (node (ref "C10") (pin "1") (pinfunction "1_1") (pintype "passive"))
      (node (ref "C11") (pin "2") (pinfunction "2_2") (pintype "passive"))
      (node (ref "C12") (pin "2") (pinfunction "2_2") (pintype "passive"))
      (node (ref "C2") (pin "2") (pinfunction "2_2") (pintype "passive"))
      (node (ref "C3") (pin "2") (pinfunction "2_2") (pintype "passive"))
      (node (ref "C4") (pin "2") (pinfunction "2_2") (pintype "passive"))
      (node (ref "C5") (pin "2") (pinfunction "2_2") (pintype "passive"))
      (node (ref "C6") (pin "2") (pinfunction "2_2") (pintype "passive"))
      (node (ref "C7") (pin "2") (pinfunction "2_2") (pintype "passive"))
      (node (ref "C8") (pin "2") (pinfunction "2_2") (pintype "passive"))
      (node (ref "C9") (pin "1") (pinfunction "1_1") (pintype "passive"))
      (node (ref "CS_1") (pin "BW_SEL") (pinfunction "BW_SEL_BW_SEL") (pintype "bidirectional"))
      (node (ref "CS_1") (pin "GND") (pinfunction "GND_GND") (pintype "bidirectional"))
      (node (ref "CS_1") (pin "IP+1") (pinfunction "IP+1_IP+1") (pintype "bidirectional"))
      (node (ref "CS_1") (pin "IP+2") (pinfunction "IP+2_IP+2") (pintype "bidirectional"))
      (node (ref "CS_2") (pin "BW_SEL") (pinfunction "BW_SEL_BW_SEL") (pintype "bidirectional"))
      (node (ref "CS_2") (pin "GND") (pinfunction "GND_GND") (pintype "bidirectional"))
      (node (ref "CS_2") (pin "IP+1") (pinfunction "IP+1_IP+1") (pintype "bidirectional"))
      (node (ref "CS_2") (pin "IP+2") (pinfunction "IP+2_IP+2") (pintype "bidirectional"))
      (node (ref "CS_3") (pin "BW_SEL") (pinfunction "BW_SEL_BW_SEL") (pintype "bidirectional"))
      (node (ref "CS_3") (pin "GND") (pinfunction "GND_GND") (pintype "bidirectional"))
      (node (ref "CS_3") (pin "IP+1") (pinfunction "IP+1_IP+1") (pintype "bidirectional"))
      (node (ref "CS_3") (pin "IP+2") (pinfunction "IP+2_IP+2") (pintype "bidirectional"))
      (node (ref "CS_4") (pin "BW_SEL") (pinfunction "BW_SEL_BW_SEL") (pintype "bidirectional"))
      (node (ref "CS_4") (pin "GND") (pinfunction "GND_GND") (pintype "bidirectional"))
      (node (ref "CS_4") (pin "IP+1") (pinfunction "IP+1_IP+1") (pintype "bidirectional"))
      (node (ref "CS_4") (pin "IP+2") (pinfunction "IP+2_IP+2") (pintype "bidirectional"))
      (node (ref "CS_5") (pin "BW_SEL") (pinfunction "BW_SEL_BW_SEL") (pintype "bidirectional"))
      (node (ref "CS_5") (pin "GND") (pinfunction "GND_GND") (pintype "bidirectional"))
      (node (ref "CS_5") (pin "IP+1") (pinfunction "IP+1_IP+1") (pintype "bidirectional"))
      (node (ref "CS_5") (pin "IP+2") (pinfunction "IP+2_IP+2") (pintype "bidirectional"))
      (node (ref "CS_6") (pin "BW_SEL") (pinfunction "BW_SEL_BW_SEL") (pintype "bidirectional"))
      (node (ref "CS_6") (pin "GND") (pinfunction "GND_GND") (pintype "bidirectional"))
      (node (ref "CS_6") (pin "IP+1") (pinfunction "IP+1_IP+1") (pintype "bidirectional"))
      (node (ref "CS_6") (pin "IP+2") (pinfunction "IP+2_IP+2") (pintype "bidirectional"))
      (node (ref "CS_7") (pin "BW_SEL") (pinfunction "BW_SEL_BW_SEL") (pintype "bidirectional"))
      (node (ref "CS_7") (pin "GND") (pinfunction "GND_GND") (pintype "bidirectional"))
      (node (ref "CS_7") (pin "IP+1") (pinfunction "IP+1_IP+1") (pintype "bidirectional"))
      (node (ref "CS_7") (pin "IP+2") (pinfunction "IP+2_IP+2") (pintype "bidirectional"))
      (node (ref "CS_8") (pin "BW_SEL") (pinfunction "BW_SEL_BW_SEL") (pintype "bidirectional"))
      (node (ref "CS_8") (pin "GND") (pinfunction "GND_GND") (pintype "bidirectional"))
      (node (ref "CS_8") (pin "IP+1") (pinfunction "IP+1_IP+1") (pintype "bidirectional"))
      (node (ref "CS_8") (pin "IP+2") (pinfunction "IP+2_IP+2") (pintype "bidirectional"))
      (node (ref "D1") (pin "C") (pinfunction "C_C") (pintype "passive"))
      (node (ref "D2") (pin "C") (pinfunction "C_C") (pintype "passive"))
      (node (ref "EDGE_CONNECTOR") (pin "10") (pinfunction "GND_10") (pintype "bidirectional"))
      (node (ref "EDGE_CONNECTOR") (pin "4") (pinfunction "GND_4") (pintype "bidirectional"))
      (node (ref "EDGE_CONNECTOR") (pin "47") (pinfunction "GND_47") (pintype "bidirectional"))
      (node (ref "EDGE_CONNECTOR") (pin "48") (pinfunction "GND_48") (pintype "bidirectional"))
      (node (ref "EDGE_CONNECTOR") (pin "49") (pinfunction "GND_49") (pintype "bidirectional"))
      (node (ref "EDGE_CONNECTOR") (pin "5") (pinfunction "GND_5") (pintype "bidirectional"))
      (node (ref "EDGE_CONNECTOR") (pin "51") (pinfunction "GND_51") (pintype "bidirectional"))
      (node (ref "EDGE_CONNECTOR") (pin "52") (pinfunction "GND_52") (pintype "bidirectional"))
      (node (ref "EDGE_CONNECTOR") (pin "53") (pinfunction "GND_53") (pintype "bidirectional"))
      (node (ref "EDGE_CONNECTOR") (pin "6") (pinfunction "GND_6") (pintype "bidirectional"))
      (node (ref "EDGE_CONNECTOR") (pin "8") (pinfunction "GND_8") (pintype "bidirectional"))
      (node (ref "EDGE_CONNECTOR") (pin "9") (pinfunction "GND_9") (pintype "bidirectional"))
      (node (ref "IC2") (pin "3") (pinfunction "GND_3") (pintype "power_in"))
      (node (ref "IC3") (pin "7") (pinfunction "VSS_7") (pintype "power_in"))
      (node (ref "POWER_INPUT") (pin "1-") (pinfunction "1-_1-") (pintype "bidirectional"))
      (node (ref "POWER_INPUT") (pin "2-") (pinfunction "2-_2-") (pintype "bidirectional"))
      (node (ref "POWER_INPUT") (pin "3-") (pinfunction "3-_3-") (pintype "bidirectional"))
      (node (ref "POWER_INPUT") (pin "4-") (pinfunction "4-_4-") (pintype "bidirectional"))
      (node (ref "POWER_INPUT") (pin "5-") (pinfunction "5-_5-") (pintype "bidirectional"))
      (node (ref "POWER_INPUT") (pin "6-") (pinfunction "6-_6-") (pintype "bidirectional"))
      (node (ref "POWER_INPUT") (pin "7-") (pinfunction "7-_7-") (pintype "bidirectional"))
      (node (ref "Q1") (pin "2") (pinfunction "S_2") (pintype "bidirectional"))
      (node (ref "Q2") (pin "2") (pinfunction "S_2") (pintype "bidirectional"))
      (node (ref "Q3") (pin "2") (pinfunction "S_2") (pintype "bidirectional"))
      (node (ref "Q4") (pin "2") (pinfunction "S_2") (pintype "bidirectional"))
      (node (ref "Q5") (pin "2") (pinfunction "S_2") (pintype "bidirectional"))
      (node (ref "Q6") (pin "2") (pinfunction "S_2") (pintype "bidirectional"))
      (node (ref "Q7") (pin "2") (pinfunction "S_2") (pintype "bidirectional"))
      (node (ref "Q8") (pin "2") (pinfunction "S_2") (pintype "bidirectional"))
      (node (ref "R11") (pin "1") (pinfunction "1_1") (pintype "passive"))
      (node (ref "R14") (pin "1") (pinfunction "1_1") (pintype "passive"))
      (node (ref "R17") (pin "1") (pinfunction "1_1") (pintype "passive"))
      (node (ref "R21") (pin "1") (pinfunction "1_1") (pintype "passive"))
      (node (ref "R24") (pin "1") (pinfunction "1_1") (pintype "passive"))
      (node (ref "R26") (pin "1") (pinfunction "1_1") (pintype "passive"))
      (node (ref "R3") (pin "1") (pinfunction "1_1") (pintype "passive"))
      (node (ref "R5") (pin "1") (pinfunction "1_1") (pintype "passive"))
      (node (ref "R8") (pin "1") (pinfunction "1_1") (pintype "passive"))
      (node (ref "U$11") (pin "GND") (pinfunction "GND_GND") (pintype "bidirectional"))
    )
    (net (code "36") (name "Net-(24-PIN_CONNECTOR-Pad1,BLUE)") (class "Default")
      (node (ref "24-PIN_CONNECTOR") (pin "1,BLUE") (pinfunction "1,BLUE_1,BLUE") (pintype "bidirectional"))
      (node (ref "3-PIN_4") (pin "BLUE") (pinfunction "BLUE_BLUE") (pintype "bidirectional"))
    )
    (net (code "37") (name "Net-(24-PIN_CONNECTOR-Pad1,GREEN)") (class "Default")
      (node (ref "24-PIN_CONNECTOR") (pin "1,GREEN") (pinfunction "1,GREEN_1,GREEN") (pintype "bidirectional"))
      (node (ref "3-PIN_4") (pin "GREEN") (pinfunction "GREEN_GREEN") (pintype "bidirectional"))
    )
    (net (code "38") (name "Net-(24-PIN_CONNECTOR-Pad1,WHITE)") (class "Default")
      (node (ref "24-PIN_CONNECTOR") (pin "1,WHITE") (pinfunction "1,WHITE_1,WHITE") (pintype "bidirectional"))
      (node (ref "3-PIN_4") (pin "WHITE") (pinfunction "WHITE_WHITE") (pintype "bidirectional"))
    )
    (net (code "39") (name "Net-(24-PIN_CONNECTOR-Pad2,BLUE)") (class "Default")
      (node (ref "24-PIN_CONNECTOR") (pin "2,BLUE") (pinfunction "2,BLUE_2,BLUE") (pintype "bidirectional"))
      (node (ref "3-PIN_8") (pin "BLUE") (pinfunction "BLUE_BLUE") (pintype "bidirectional"))
    )
    (net (code "40") (name "Net-(24-PIN_CONNECTOR-Pad2,GREEN)") (class "Default")
      (node (ref "24-PIN_CONNECTOR") (pin "2,GREEN") (pinfunction "2,GREEN_2,GREEN") (pintype "bidirectional"))
      (node (ref "3-PIN_8") (pin "GREEN") (pinfunction "GREEN_GREEN") (pintype "bidirectional"))
    )
    (net (code "41") (name "Net-(24-PIN_CONNECTOR-Pad2,WHITE)") (class "Default")
      (node (ref "24-PIN_CONNECTOR") (pin "2,WHITE") (pinfunction "2,WHITE_2,WHITE") (pintype "bidirectional"))
      (node (ref "3-PIN_8") (pin "WHITE") (pinfunction "WHITE_WHITE") (pintype "bidirectional"))
    )
    (net (code "42") (name "Net-(24-PIN_CONNECTOR-Pad3,BLUE)") (class "Default")
      (node (ref "24-PIN_CONNECTOR") (pin "3,BLUE") (pinfunction "3,BLUE_3,BLUE") (pintype "bidirectional"))
      (node (ref "3-PIN_3") (pin "BLUE") (pinfunction "BLUE_BLUE") (pintype "bidirectional"))
    )
    (net (code "43") (name "Net-(24-PIN_CONNECTOR-Pad3,GREEN)") (class "Default")
      (node (ref "24-PIN_CONNECTOR") (pin "3,GREEN") (pinfunction "3,GREEN_3,GREEN") (pintype "bidirectional"))
      (node (ref "3-PIN_3") (pin "GREEN") (pinfunction "GREEN_GREEN") (pintype "bidirectional"))
    )
    (net (code "44") (name "Net-(24-PIN_CONNECTOR-Pad3,WHITE)") (class "Default")
      (node (ref "24-PIN_CONNECTOR") (pin "3,WHITE") (pinfunction "3,WHITE_3,WHITE") (pintype "bidirectional"))
      (node (ref "3-PIN_3") (pin "WHITE") (pinfunction "WHITE_WHITE") (pintype "bidirectional"))
    )
    (net (code "45") (name "Net-(24-PIN_CONNECTOR-Pad4,BLUE)") (class "Default")
      (node (ref "24-PIN_CONNECTOR") (pin "4,BLUE") (pinfunction "4,BLUE_4,BLUE") (pintype "bidirectional"))
      (node (ref "3-PIN_7") (pin "BLUE") (pinfunction "BLUE_BLUE") (pintype "bidirectional"))
    )
    (net (code "46") (name "Net-(24-PIN_CONNECTOR-Pad4,GREEN)") (class "Default")
      (node (ref "24-PIN_CONNECTOR") (pin "4,GREEN") (pinfunction "4,GREEN_4,GREEN") (pintype "bidirectional"))
      (node (ref "3-PIN_7") (pin "GREEN") (pinfunction "GREEN_GREEN") (pintype "bidirectional"))
    )
    (net (code "47") (name "Net-(24-PIN_CONNECTOR-Pad4,WHITE)") (class "Default")
      (node (ref "24-PIN_CONNECTOR") (pin "4,WHITE") (pinfunction "4,WHITE_4,WHITE") (pintype "bidirectional"))
      (node (ref "3-PIN_7") (pin "WHITE") (pinfunction "WHITE_WHITE") (pintype "bidirectional"))
    )
    (net (code "48") (name "Net-(24-PIN_CONNECTOR-Pad5,BLUE)") (class "Default")
      (node (ref "24-PIN_CONNECTOR") (pin "5,BLUE") (pinfunction "5,BLUE_5,BLUE") (pintype "bidirectional"))
      (node (ref "3-PIN_2") (pin "BLUE") (pinfunction "BLUE_BLUE") (pintype "bidirectional"))
    )
    (net (code "49") (name "Net-(24-PIN_CONNECTOR-Pad5,GREEN)") (class "Default")
      (node (ref "24-PIN_CONNECTOR") (pin "5,GREEN") (pinfunction "5,GREEN_5,GREEN") (pintype "bidirectional"))
      (node (ref "3-PIN_2") (pin "GREEN") (pinfunction "GREEN_GREEN") (pintype "bidirectional"))
    )
    (net (code "50") (name "Net-(24-PIN_CONNECTOR-Pad5,WHITE)") (class "Default")
      (node (ref "24-PIN_CONNECTOR") (pin "5,WHITE") (pinfunction "5,WHITE_5,WHITE") (pintype "bidirectional"))
      (node (ref "3-PIN_2") (pin "WHITE") (pinfunction "WHITE_WHITE") (pintype "bidirectional"))
    )
    (net (code "51") (name "Net-(24-PIN_CONNECTOR-Pad6,BLUE)") (class "Default")
      (node (ref "24-PIN_CONNECTOR") (pin "6,BLUE") (pinfunction "6,BLUE_6,BLUE") (pintype "bidirectional"))
      (node (ref "3-PIN_6") (pin "BLUE") (pinfunction "BLUE_BLUE") (pintype "bidirectional"))
    )
    (net (code "52") (name "Net-(24-PIN_CONNECTOR-Pad6,GREEN)") (class "Default")
      (node (ref "24-PIN_CONNECTOR") (pin "6,GREEN") (pinfunction "6,GREEN_6,GREEN") (pintype "bidirectional"))
      (node (ref "3-PIN_6") (pin "GREEN") (pinfunction "GREEN_GREEN") (pintype "bidirectional"))
    )
    (net (code "53") (name "Net-(24-PIN_CONNECTOR-Pad6,WHITE)") (class "Default")
      (node (ref "24-PIN_CONNECTOR") (pin "6,WHITE") (pinfunction "6,WHITE_6,WHITE") (pintype "bidirectional"))
      (node (ref "3-PIN_6") (pin "WHITE") (pinfunction "WHITE_WHITE") (pintype "bidirectional"))
    )
    (net (code "54") (name "Net-(24-PIN_CONNECTOR-Pad7,BLUE)") (class "Default")
      (node (ref "24-PIN_CONNECTOR") (pin "7,BLUE") (pinfunction "7,BLUE_7,BLUE") (pintype "bidirectional"))
      (node (ref "3-PIN_1") (pin "BLUE") (pinfunction "BLUE_BLUE") (pintype "bidirectional"))
    )
    (net (code "55") (name "Net-(24-PIN_CONNECTOR-Pad7,GREEN)") (class "Default")
      (node (ref "24-PIN_CONNECTOR") (pin "7,GREEN") (pinfunction "7,GREEN_7,GREEN") (pintype "bidirectional"))
      (node (ref "3-PIN_1") (pin "GREEN") (pinfunction "GREEN_GREEN") (pintype "bidirectional"))
    )
    (net (code "56") (name "Net-(24-PIN_CONNECTOR-Pad7,WHITE)") (class "Default")
      (node (ref "24-PIN_CONNECTOR") (pin "7,WHITE") (pinfunction "7,WHITE_7,WHITE") (pintype "bidirectional"))
      (node (ref "3-PIN_1") (pin "WHITE") (pinfunction "WHITE_WHITE") (pintype "bidirectional"))
    )
    (net (code "57") (name "Net-(24-PIN_CONNECTOR-Pad8,BLUE)") (class "Default")
      (node (ref "24-PIN_CONNECTOR") (pin "8,BLUE") (pinfunction "8,BLUE_8,BLUE") (pintype "bidirectional"))
      (node (ref "3-PIN_5") (pin "BLUE") (pinfunction "BLUE_BLUE") (pintype "bidirectional"))
    )
    (net (code "58") (name "Net-(24-PIN_CONNECTOR-Pad8,GREEN)") (class "Default")
      (node (ref "24-PIN_CONNECTOR") (pin "8,GREEN") (pinfunction "8,GREEN_8,GREEN") (pintype "bidirectional"))
      (node (ref "3-PIN_5") (pin "GREEN") (pinfunction "GREEN_GREEN") (pintype "bidirectional"))
    )
    (net (code "59") (name "Net-(24-PIN_CONNECTOR-Pad8,WHITE)") (class "Default")
      (node (ref "24-PIN_CONNECTOR") (pin "8,WHITE") (pinfunction "8,WHITE_8,WHITE") (pintype "bidirectional"))
      (node (ref "3-PIN_5") (pin "WHITE") (pinfunction "WHITE_WHITE") (pintype "bidirectional"))
    )
    (net (code "60") (name "Net-(D1-PadA)") (class "Default")
      (node (ref "D1") (pin "A") (pinfunction "A_A") (pintype "passive"))
      (node (ref "R1") (pin "1") (pinfunction "1_1") (pintype "passive"))
      (node (ref "R38") (pin "1") (pinfunction "1_1") (pintype "passive"))
    )
    (net (code "61") (name "Net-(D2-PadA)") (class "Default")
      (node (ref "D2") (pin "A") (pinfunction "A_A") (pintype "passive"))
      (node (ref "R28") (pin "1") (pinfunction "1_1") (pintype "passive"))
    )
    (net (code "62") (name "Net-(D3-PadA)") (class "Default")
      (node (ref "D3") (pin "A") (pinfunction "A_A") (pintype "passive"))
      (node (ref "R18") (pin "1") (pinfunction "1_1") (pintype "passive"))
    )
    (net (code "63") (name "Net-(D4-PadA)") (class "Default")
      (node (ref "D4") (pin "A") (pinfunction "A_A") (pintype "passive"))
      (node (ref "R6") (pin "1") (pinfunction "1_1") (pintype "passive"))
    )
    (net (code "64") (name "Net-(D5-PadA)") (class "Default")
      (node (ref "D5") (pin "A") (pinfunction "A_A") (pintype "passive"))
      (node (ref "R9") (pin "1") (pinfunction "1_1") (pintype "passive"))
    )
    (net (code "65") (name "Net-(D6-PadA)") (class "Default")
      (node (ref "D6") (pin "A") (pinfunction "A_A") (pintype "passive"))
      (node (ref "R12") (pin "1") (pinfunction "1_1") (pintype "passive"))
    )
    (net (code "66") (name "Net-(D7-PadA)") (class "Default")
      (node (ref "D7") (pin "A") (pinfunction "A_A") (pintype "passive"))
      (node (ref "R15") (pin "1") (pinfunction "1_1") (pintype "passive"))
    )
    (net (code "67") (name "Net-(D8-PadA)") (class "Default")
      (node (ref "D8") (pin "A") (pinfunction "A_A") (pintype "passive"))
      (node (ref "R19") (pin "1") (pinfunction "1_1") (pintype "passive"))
    )
    (net (code "68") (name "Net-(D9-PadA)") (class "Default")
      (node (ref "D9") (pin "A") (pinfunction "A_A") (pintype "passive"))
      (node (ref "R22") (pin "1") (pinfunction "1_1") (pintype "passive"))
    )
    (net (code "69") (name "Net-(D10-PadA)") (class "Default")
      (node (ref "D10") (pin "A") (pinfunction "A_A") (pintype "passive"))
      (node (ref "R25") (pin "1") (pinfunction "1_1") (pintype "passive"))
    )
    (net (code "70") (name "Net-(IC2A-I0)") (class "Default")
      (node (ref "IC2") (pin "1") (pinfunction "I0_1") (pintype "input"))
      (node (ref "IC3") (pin "1") (pinfunction "O_1") (pintype "output"))
    )
    (net (code "71") (name "Net-(IC2A-I1)") (class "Default")
      (node (ref "IC2") (pin "2") (pinfunction "I1_2") (pintype "input"))
      (node (ref "IC3") (pin "13") (pinfunction "O_13") (pintype "output"))
    )
    (net (code "72") (name "Net-(IC2A-O)") (class "Default")
      (node (ref "IC2") (pin "4") (pinfunction "O_4") (pintype "output"))
      (node (ref "R28") (pin "2") (pinfunction "2_2") (pintype "passive"))
    )
    (net (code "73") (name "Net-(Q1-D)") (class "Default")
      (node (ref "D3") (pin "C") (pinfunction "C_C") (pintype "passive"))
      (node (ref "Q1") (pin "3") (pinfunction "D_3") (pintype "bidirectional"))
    )
    (net (code "74") (name "Net-(Q2-D)") (class "Default")
      (node (ref "D4") (pin "C") (pinfunction "C_C") (pintype "passive"))
      (node (ref "Q2") (pin "3") (pinfunction "D_3") (pintype "bidirectional"))
    )
    (net (code "75") (name "Net-(Q3-D)") (class "Default")
      (node (ref "D5") (pin "C") (pinfunction "C_C") (pintype "passive"))
      (node (ref "Q3") (pin "3") (pinfunction "D_3") (pintype "bidirectional"))
    )
    (net (code "76") (name "Net-(Q4-D)") (class "Default")
      (node (ref "D6") (pin "C") (pinfunction "C_C") (pintype "passive"))
      (node (ref "Q4") (pin "3") (pinfunction "D_3") (pintype "bidirectional"))
    )
    (net (code "77") (name "Net-(Q5-D)") (class "Default")
      (node (ref "D7") (pin "C") (pinfunction "C_C") (pintype "passive"))
      (node (ref "Q5") (pin "3") (pinfunction "D_3") (pintype "bidirectional"))
    )
    (net (code "78") (name "Net-(Q6-D)") (class "Default")
      (node (ref "D8") (pin "C") (pinfunction "C_C") (pintype "passive"))
      (node (ref "Q6") (pin "3") (pinfunction "D_3") (pintype "bidirectional"))
    )
    (net (code "79") (name "Net-(Q7-D)") (class "Default")
      (node (ref "D9") (pin "C") (pinfunction "C_C") (pintype "passive"))
      (node (ref "Q7") (pin "3") (pinfunction "D_3") (pintype "bidirectional"))
    )
    (net (code "80") (name "Net-(Q8-D)") (class "Default")
      (node (ref "D10") (pin "C") (pinfunction "C_C") (pintype "passive"))
      (node (ref "Q8") (pin "3") (pinfunction "D_3") (pintype "bidirectional"))
    )
    (net (code "81") (name "Net-(R26-Pad2)") (class "Default")
      (node (ref "R26") (pin "2") (pinfunction "2_2") (pintype "passive"))
      (node (ref "R27") (pin "1") (pinfunction "1_1") (pintype "passive"))
      (node (ref "U$11") (pin "A0") (pinfunction "A0_A0") (pintype "bidirectional"))
      (node (ref "U$11") (pin "A1") (pinfunction "A1_A1") (pintype "bidirectional"))
    )
    (net (code "82") (name "PWM_1") (class "Default")
      (node (ref "EDGE_CONNECTOR") (pin "20") (pinfunction "PWM_1_20") (pintype "bidirectional"))
      (node (ref "U$1") (pin "PWM") (pinfunction "PWM_PWM") (pintype "bidirectional"))
    )
    (net (code "83") (name "PWM_2") (class "Default")
      (node (ref "EDGE_CONNECTOR") (pin "21") (pinfunction "PWM_2_21") (pintype "bidirectional"))
      (node (ref "U$2") (pin "PWM") (pinfunction "PWM_PWM") (pintype "bidirectional"))
    )
    (net (code "84") (name "PWM_3") (class "Default")
      (node (ref "EDGE_CONNECTOR") (pin "22") (pinfunction "PWM_3_22") (pintype "bidirectional"))
      (node (ref "U$3") (pin "PWM") (pinfunction "PWM_PWM") (pintype "bidirectional"))
    )
    (net (code "85") (name "PWM_4") (class "Default")
      (node (ref "EDGE_CONNECTOR") (pin "23") (pinfunction "PWM_4_23") (pintype "bidirectional"))
      (node (ref "U$4") (pin "PWM") (pinfunction "PWM_PWM") (pintype "bidirectional"))
    )
    (net (code "86") (name "PWM_5") (class "Default")
      (node (ref "EDGE_CONNECTOR") (pin "24") (pinfunction "PWM_5_24") (pintype "bidirectional"))
      (node (ref "U$5") (pin "PWM") (pinfunction "PWM_PWM") (pintype "bidirectional"))
    )
    (net (code "87") (name "PWM_6") (class "Default")
      (node (ref "EDGE_CONNECTOR") (pin "25") (pinfunction "PWM_6_25") (pintype "bidirectional"))
      (node (ref "U$6") (pin "PWM") (pinfunction "PWM_PWM") (pintype "bidirectional"))
    )
    (net (code "88") (name "PWM_7") (class "Default")
      (node (ref "EDGE_CONNECTOR") (pin "26") (pinfunction "PWM_7_26") (pintype "bidirectional"))
      (node (ref "U$7") (pin "PWM") (pinfunction "PWM_PWM") (pintype "bidirectional"))
    )
    (net (code "89") (name "PWM_8") (class "Default")
      (node (ref "EDGE_CONNECTOR") (pin "27") (pinfunction "PWM_8_27") (pintype "bidirectional"))
      (node (ref "U$8") (pin "PWM") (pinfunction "PWM_PWM") (pintype "bidirectional"))
    )
    (net (code "90") (name "SCL") (class "Default")
      (node (ref "EDGE_CONNECTOR") (pin "31") (pinfunction "BACKPLANE_SCL_31") (pintype "bidirectional"))
      (node (ref "U$11") (pin "SCL") (pinfunction "SCL_SCL") (pintype "bidirectional"))
    )
    (net (code "91") (name "SDA") (class "Default")
      (node (ref "EDGE_CONNECTOR") (pin "32") (pinfunction "BACKPLANE_SDA_32") (pintype "bidirectional"))
      (node (ref "U$11") (pin "SDA") (pinfunction "SDA_SDA") (pintype "bidirectional"))
    )
    (net (code "92") (name "VOLTAGE_INPUT") (class "Default")
      (node (ref "2-PIN_1") (pin "P$2") (pinfunction "RED_P$2") (pintype "bidirectional"))
      (node (ref "2-PIN_2") (pin "P$2") (pinfunction "RED_P$2") (pintype "bidirectional"))
      (node (ref "2-PIN_3") (pin "P$2") (pinfunction "RED_P$2") (pintype "bidirectional"))
      (node (ref "2-PIN_4") (pin "P$2") (pinfunction "RED_P$2") (pintype "bidirectional"))
      (node (ref "2-PIN_5") (pin "P$2") (pinfunction "RED_P$2") (pintype "bidirectional"))
      (node (ref "2-PIN_6") (pin "P$2") (pinfunction "RED_P$2") (pintype "bidirectional"))
      (node (ref "2-PIN_7") (pin "P$2") (pinfunction "RED_P$2") (pintype "bidirectional"))
      (node (ref "2-PIN_8") (pin "P$2") (pinfunction "RED_P$2") (pintype "bidirectional"))
      (node (ref "POWER_INPUT") (pin "1+") (pinfunction "1+_1+") (pintype "bidirectional"))
      (node (ref "POWER_INPUT") (pin "2+") (pinfunction "2+_2+") (pintype "bidirectional"))
      (node (ref "POWER_INPUT") (pin "3+") (pinfunction "3+_3+") (pintype "bidirectional"))
      (node (ref "POWER_INPUT") (pin "4+") (pinfunction "4+_4+") (pintype "bidirectional"))
      (node (ref "POWER_INPUT") (pin "5+") (pinfunction "5+_5+") (pintype "bidirectional"))
      (node (ref "POWER_INPUT") (pin "6+") (pinfunction "6+_6+") (pintype "bidirectional"))
      (node (ref "POWER_INPUT") (pin "7+") (pinfunction "7+_7+") (pintype "bidirectional"))
      (node (ref "R1") (pin "2") (pinfunction "2_2") (pintype "passive"))
      (node (ref "R38") (pin "2") (pinfunction "2_2") (pintype "passive"))
    )
    (net (code "93") (name "unconnected-(EDGE_CONNECTOR-3.3V_ON{slash}OFF-Pad14)") (class "Default")
      (node (ref "EDGE_CONNECTOR") (pin "14") (pinfunction "3.3V_ON/OFF_14") (pintype "bidirectional"))
    )
    (net (code "94") (name "unconnected-(EDGE_CONNECTOR-5V_ON_OFF-Pad15)") (class "Default")
      (node (ref "EDGE_CONNECTOR") (pin "15") (pinfunction "5V_ON_OFF_15") (pintype "bidirectional"))
    )
    (net (code "95") (name "unconnected-(EDGE_CONNECTOR-12V_ON{slash}OFF-Pad16)") (class "Default")
      (node (ref "EDGE_CONNECTOR") (pin "16") (pinfunction "12V_ON/OFF_16") (pintype "bidirectional"))
    )
    (net (code "96") (name "unconnected-(EDGE_CONNECTOR-ACOUSTIC_ON{slash}OFF-Pad17)") (class "Default")
      (node (ref "EDGE_CONNECTOR") (pin "17") (pinfunction "ACOUSTIC_ON/OFF_17") (pintype "bidirectional"))
    )
    (net (code "97") (name "unconnected-(EDGE_CONNECTOR-CONTROL_SIGNAL-Pad7)") (class "Default")
      (node (ref "EDGE_CONNECTOR") (pin "7") (pinfunction "CONTROL_SIGNAL_7") (pintype "bidirectional"))
    )
    (net (code "98") (name "unconnected-(EDGE_CONNECTOR-JETSON_ON{slash}OFF-Pad18)") (class "Default")
      (node (ref "EDGE_CONNECTOR") (pin "18") (pinfunction "JETSON_ON/OFF_18") (pintype "bidirectional"))
    )
    (net (code "99") (name "unconnected-(EDGE_CONNECTOR-KILL_SWITCH-Pad37)") (class "Default")
      (node (ref "EDGE_CONNECTOR") (pin "37") (pinfunction "KILL_SWITCH_37") (pintype "output"))
    )
    (net (code "100") (name "unconnected-(EDGE_CONNECTOR-MOBO_ON{slash}OFF-Pad19)") (class "Default")
      (node (ref "EDGE_CONNECTOR") (pin "19") (pinfunction "MOBO_ON/OFF_19") (pintype "bidirectional"))
    )
    (net (code "101") (name "unconnected-(EDGE_CONNECTOR-PLTA_ON{slash}OFF-Pad50)") (class "Default")
      (node (ref "EDGE_CONNECTOR") (pin "50") (pinfunction "PLTA_ON/OFF_50") (pintype "bidirectional"))
    )
    (net (code "102") (name "unconnected-(EDGE_CONNECTOR-ROBOT_SCL-Pad29)") (class "Default")
      (node (ref "EDGE_CONNECTOR") (pin "29") (pinfunction "ROBOT_SCL_29") (pintype "bidirectional"))
    )
    (net (code "103") (name "unconnected-(EDGE_CONNECTOR-ROBOT_SDA-Pad30)") (class "Default")
      (node (ref "EDGE_CONNECTOR") (pin "30") (pinfunction "ROBOT_SDA_30") (pintype "bidirectional"))
    )
    (net (code "104") (name "unconnected-(EDGE_CONNECTOR-SPARE2-Pad28)") (class "Default")
      (node (ref "EDGE_CONNECTOR") (pin "28") (pinfunction "SPARE2_28") (pintype "bidirectional"))
    )
    (net (code "105") (name "unconnected-(EDGE_CONNECTOR-SPARE3-Pad33)") (class "Default")
      (node (ref "EDGE_CONNECTOR") (pin "33") (pinfunction "SPARE3_33") (pintype "bidirectional"))
    )
    (net (code "106") (name "unconnected-(EDGE_CONNECTOR-SPARE4-Pad34)") (class "Default")
      (node (ref "EDGE_CONNECTOR") (pin "34") (pinfunction "SPARE4_34") (pintype "bidirectional"))
    )
    (net (code "107") (name "unconnected-(EDGE_CONNECTOR-SPARE5-Pad35)") (class "Default")
      (node (ref "EDGE_CONNECTOR") (pin "35") (pinfunction "SPARE5_35") (pintype "bidirectional"))
    )
    (net (code "108") (name "unconnected-(EDGE_CONNECTOR-SPARE6-Pad36)") (class "Default")
      (node (ref "EDGE_CONNECTOR") (pin "36") (pinfunction "SPARE6_36") (pintype "bidirectional"))
    )
    (net (code "109") (name "unconnected-(EDGE_CONNECTOR-SWITCH_1-Pad38)") (class "Default")
      (node (ref "EDGE_CONNECTOR") (pin "38") (pinfunction "SWITCH_1_38") (pintype "output"))
    )
    (net (code "110") (name "unconnected-(EDGE_CONNECTOR-SWITCH_2-Pad39)") (class "Default")
      (node (ref "EDGE_CONNECTOR") (pin "39") (pinfunction "SWITCH_2_39") (pintype "output"))
    )
    (net (code "111") (name "unconnected-(EDGE_CONNECTOR-SWITCH_3-Pad40)") (class "Default")
      (node (ref "EDGE_CONNECTOR") (pin "40") (pinfunction "SWITCH_3_40") (pintype "output"))
    )
    (net (code "112") (name "unconnected-(EDGE_CONNECTOR-SWITCH_4-Pad41)") (class "Default")
      (node (ref "EDGE_CONNECTOR") (pin "41") (pinfunction "SWITCH_4_41") (pintype "output"))
    )
    (net (code "113") (name "unconnected-(EDGE_CONNECTOR-SWITCH_5-Pad42)") (class "Default")
      (node (ref "EDGE_CONNECTOR") (pin "42") (pinfunction "SWITCH_5_42") (pintype "output"))
    )
    (net (code "114") (name "unconnected-(U$11-PadINT)") (class "Default")
      (node (ref "U$11") (pin "INT") (pinfunction "INT_INT") (pintype "bidirectional"))
    )
  )
)
